# S3220B1.net
KiCad netlist of a schematic drawn in Altium Designer
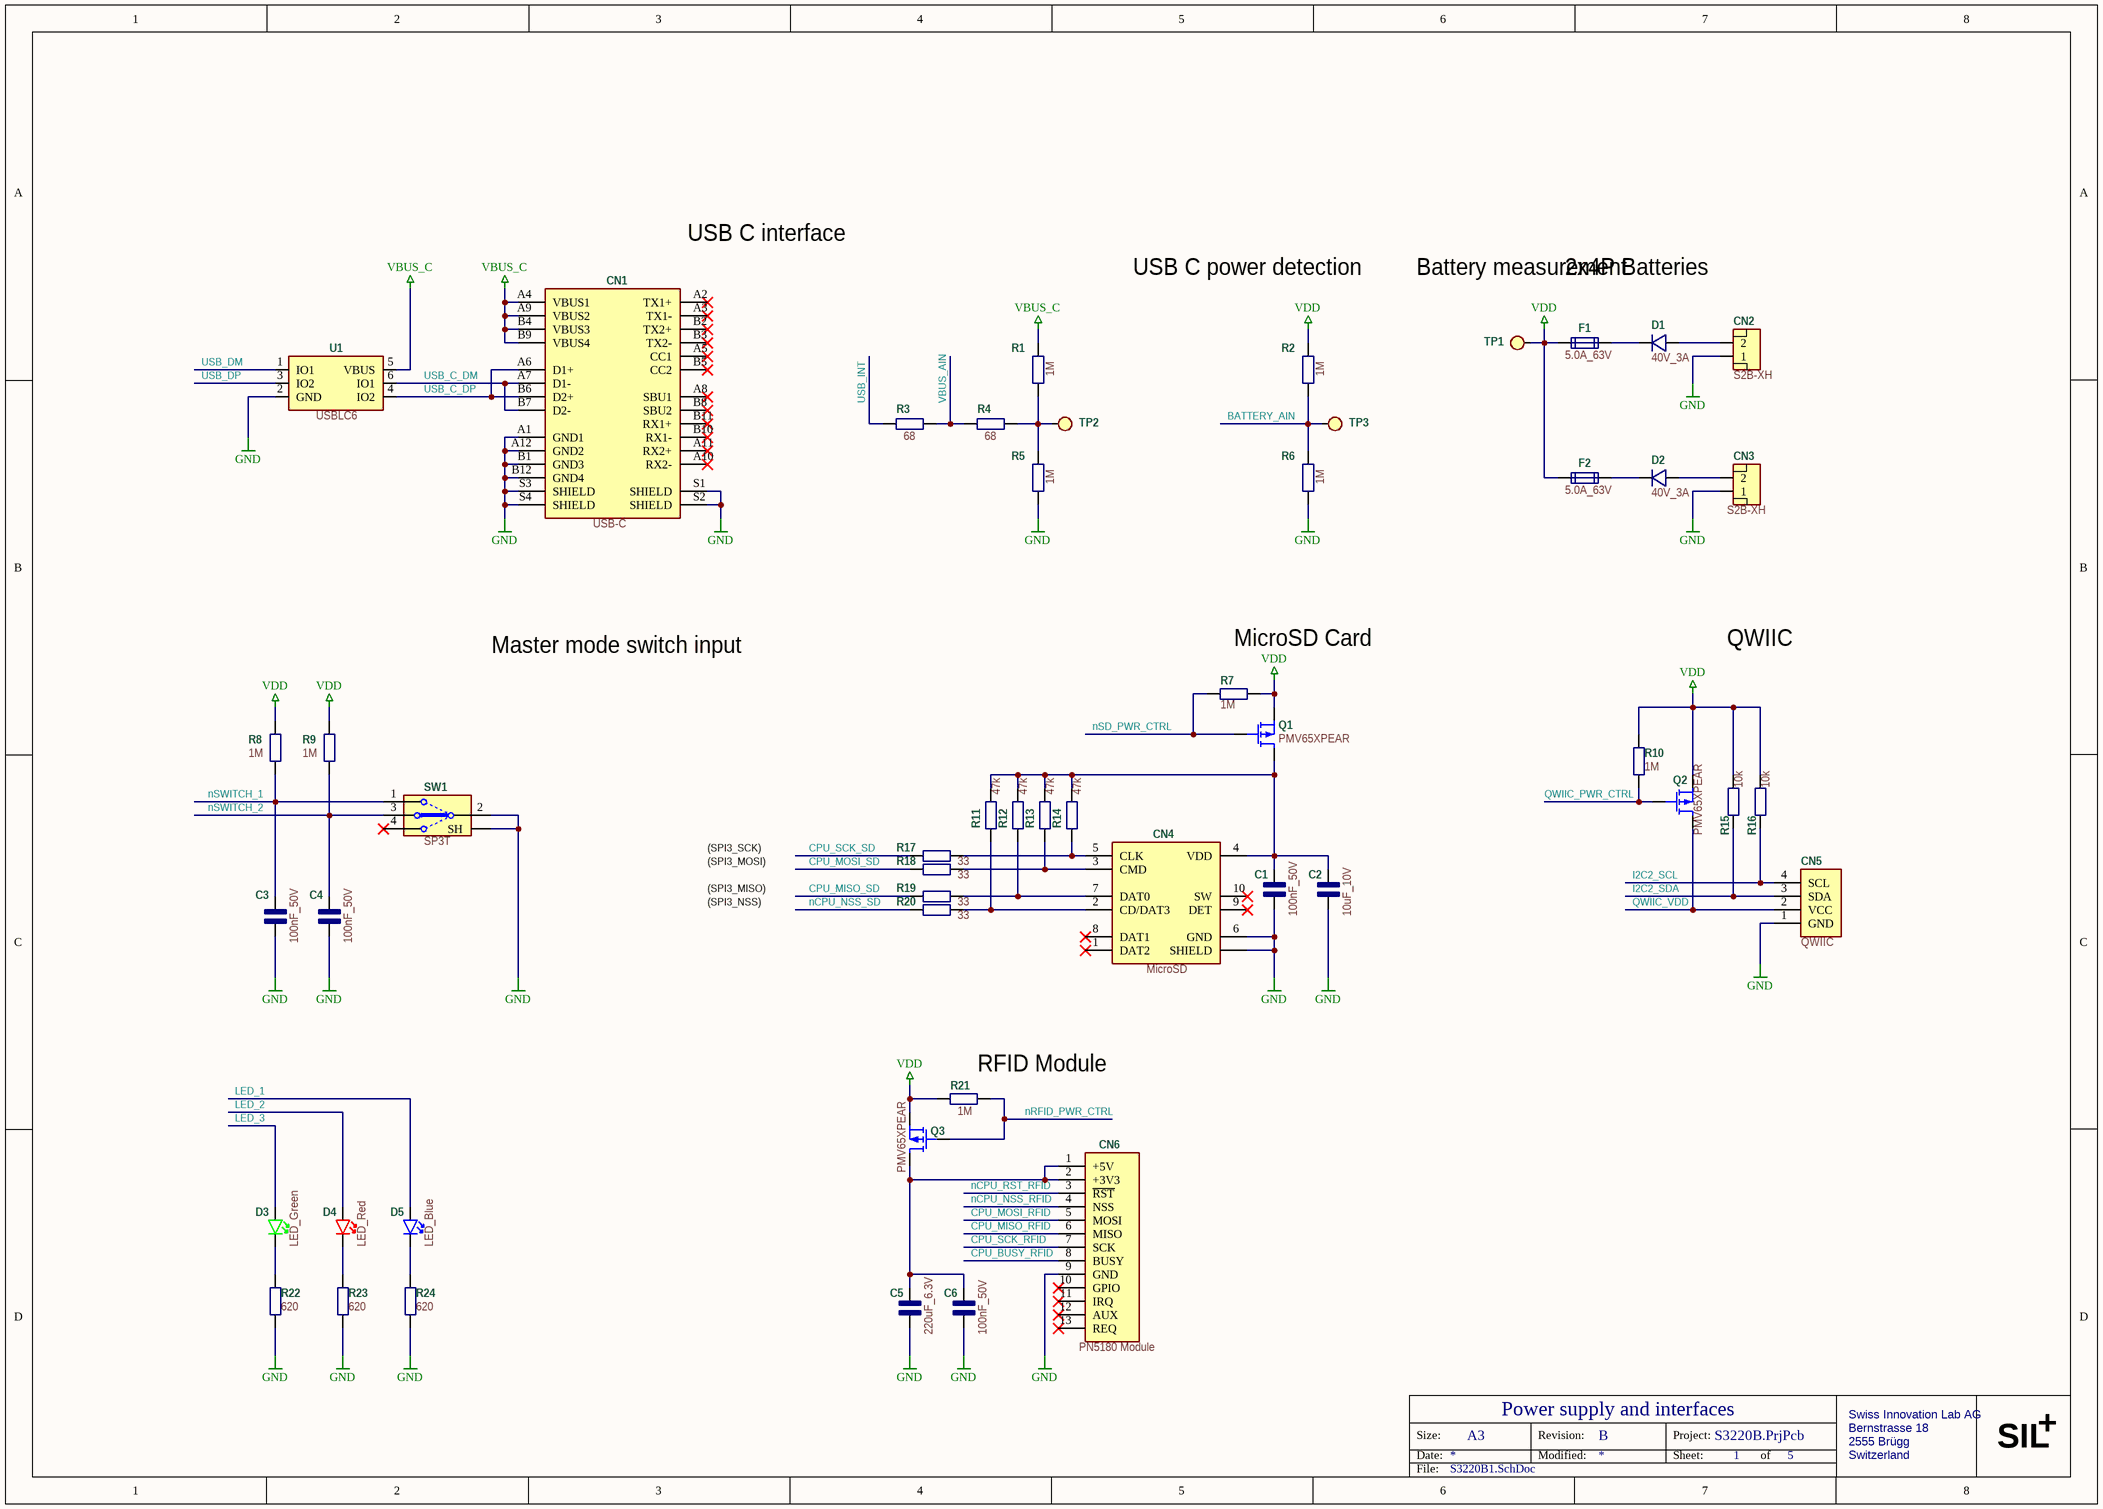
[diagram p0: S3220B1.SchDoc]

(export (version "E")
  (design (tool "Eeschema 10.0.6"))
  (components
    (comp (ref "C1")
      (value "100nF_50V")
      (footprint "SIL:C_0603")
      (description "0.1µF ±10% 50V Ceramic Capacitor X7R 0603 (1608 Metric)")
      (fields
        (field (name "MANUFACTURER") "TDK")
        (field (name "MANUFACTURER PART NUMBER") "C1608X7R1H104K080AA")
      )
      (libsource (lib "SIL") (part "C_100nF_50V"))
    )
    (comp (ref "C2")
      (value "10uF_10V")
      (footprint "SIL:C_0603")
      (description "10µF ±10% 10V Ceramic Capacitor X5R 0603 (1608 Metric)")
      (fields
        (field (name "MANUFACTURER") "Murata Electronics North America")
        (field (name "MANUFACTURER PART NUMBER") "GRM188R61A106KE69D")
      )
      (libsource (lib "SIL") (part "C_10uF_10V"))
    )
    (comp (ref "C3")
      (value "100nF_50V")
      (footprint "SIL:C_0603")
      (description "0.1µF ±10% 50V Ceramic Capacitor X7R 0603 (1608 Metric)")
      (fields
        (field (name "MANUFACTURER") "TDK")
        (field (name "MANUFACTURER PART NUMBER") "C1608X7R1H104K080AA")
      )
      (libsource (lib "SIL") (part "C_100nF_50V"))
    )
    (comp (ref "C4")
      (value "100nF_50V")
      (footprint "SIL:C_0603")
      (description "0.1µF ±10% 50V Ceramic Capacitor X7R 0603 (1608 Metric)")
      (fields
        (field (name "MANUFACTURER") "TDK")
        (field (name "MANUFACTURER PART NUMBER") "C1608X7R1H104K080AA")
      )
      (libsource (lib "SIL") (part "C_100nF_50V"))
    )
    (comp (ref "C5")
      (value "220uF_6.3V")
      (footprint "C_1206")
      (description "220µF ±20% 6.3V Ceramic Capacitor X5R 1206 (3216 Metric)")
      (fields
        (field (name "MANUFACTURER") "Murata Electronics North America")
        (field (name "MANUFACTURER PART NUMBER") "GRM31CR60J227ME11L")
      )
      (libsource (lib "SIL") (part "C_220uF_6.3V"))
    )
    (comp (ref "C6")
      (value "100nF_50V")
      (footprint "SIL:C_0603")
      (description "0.1µF ±10% 50V Ceramic Capacitor X7R 0603 (1608 Metric)")
      (fields
        (field (name "MANUFACTURER") "TDK")
        (field (name "MANUFACTURER PART NUMBER") "C1608X7R1H104K080AA")
      )
      (libsource (lib "SIL") (part "C_100nF_50V"))
    )
    (comp (ref "CN1")
      (value "USB-C")
      (footprint "CN_USB-C-RA_2")
      (fields
        (field (name "MANUFACTURER") "CUI Devices")
        (field (name "MANUFACTURER PART NUMBER") "UJ31-CH-G-SMT-TR-67")
      )
      (libsource (lib "SIL") (part "CN_USB-C-RA_2"))
    )
    (comp (ref "CN2")
      (value "S2B-XH")
      (footprint "CN_S2B-XH-A")
      (description "Connector Header Through Hole, Right Angle 2 position 0.098\" (2.50mm)")
      (fields
        (field (name "MANUFACTURER") "JST Sales America Inc.")
        (field (name "MANUFACTURER PART NUMBER") "S2B-XH-A(LF)(SN)")
      )
      (libsource (lib "SIL") (part "CN_S2B-XH"))
    )
    (comp (ref "CN3")
      (value "S2B-XH")
      (footprint "CN_S2B-XH-A")
      (description "Connector Header Through Hole, Right Angle 2 position 0.098\" (2.50mm)")
      (fields
        (field (name "MANUFACTURER") "JST Sales America Inc.")
        (field (name "MANUFACTURER PART NUMBER") "S2B-XH-A(LF)(SN)")
      )
      (libsource (lib "SIL") (part "CN_S2B-XH"))
    )
    (comp (ref "CN4")
      (value "MicroSD")
      (footprint "CN_MicroSD-Holder")
      (description "10 (8 + 2) Position Card Connector Secure Digital microSD Surface Mount, Right Angle Gold")
      (fields (field (name "MANUFACTURER") "Molex") (field (name "MANUFACTURER PART NUMBER") "5031821852"))
      (libsource (lib "SIL") (part "CN_MicroSD-Holder"))
    )
    (comp (ref "CN5")
      (value "QWIIC")
      (footprint "CN_SM04B-SRSS-TB")
      (description "Connector Header Surface Mount, Right Angle 4 position 0.039\" (1.00mm)")
      (fields
        (field (name "MANUFACTURER") "JST Sales America Inc.")
        (field (name "MANUFACTURER PART NUMBER") "SM04B-SRSS-TB(LF)(SN)")
      )
      (libsource (lib "SIL") (part "CN_QWICC"))
    )
    (comp (ref "CN6")
      (value "PN5180 Module")
      (footprint "CN_RFID-PN5180")
      (description "RFID Module PN5180")
      (fields
        (field (name "MANUFACTURER") "Swiss Innovation Lab")
        (field (name "MANUFACTURER PART NUMBER") "RFID-PN5180")
      )
      (libsource (lib "SIL") (part "CN_RFID-PN5180"))
    )
    (comp (ref "D1")
      (value "40V_3A")
      (footprint "D_DO-214AC")
      (description "Diode Schottky 40V 3A Surface Mount DO-214AC (SMA)")
      (fields
        (field (name "MANUFACTURER") "Comchip Technology")
        (field (name "MANUFACTURER PART NUMBER") "CDBA340L-HF")
      )
      (libsource (lib "SIL") (part "D_40V_3A"))
    )
    (comp (ref "D2")
      (value "40V_3A")
      (footprint "D_DO-214AC")
      (description "Diode Schottky 40V 3A Surface Mount DO-214AC (SMA)")
      (fields
        (field (name "MANUFACTURER") "Comchip Technology")
        (field (name "MANUFACTURER PART NUMBER") "CDBA340L-HF")
      )
      (libsource (lib "SIL") (part "D_40V_3A"))
    )
    (comp (ref "D3")
      (value "LED_Green")
      (footprint "LED_2-SMD_4x4")
      (description "Green 570nm LED Indication - Discrete 1.8V 2-SMD, Boomerang")
      (fields
        (field (name "MANUFACTURER") "OSRAM Opto Semiconductors Inc.")
        (field (name "MANUFACTURER PART NUMBER") "LG A67K-G2K1-24-0-2-R33-Z")
      )
      (libsource (lib "SIL") (part "D_LED_G_2mA"))
    )
    (comp (ref "D4")
      (value "LED_Red")
      (footprint "LED_2-SMD_4x4")
      (description "Red 630nm LED Indication - Discrete 1.8V 2-SMD, Boomerang")
      (fields
        (field (name "MANUFACTURER") "OSRAM Opto Semiconductors Inc.")
        (field (name "MANUFACTURER PART NUMBER") "LS A67K-J1K2-1-Z")
      )
      (libsource (lib "SIL") (part "D_LED_R_2mA"))
    )
    (comp (ref "D5")
      (value "LED_Blue")
      (footprint "LED_2-SMD_4x4")
      (description "Blue 471nm LED Indication - Discrete 3.1V 2-SMD, Boomerang")
      (fields
        (field (name "MANUFACTURER") "OSRAM Opto Semiconductors Inc.")
        (field (name "MANUFACTURER PART NUMBER") "LB A673-L2N1-35-Z")
      )
      (libsource (lib "SIL") (part "D_LED_B_10mA"))
    )
    (comp (ref "F1")
      (value "5.0A_63V")
      (footprint "F_1206")
      (description "FUSE BOARD MNT 5A 63VAC/VDC 1206")
      (fields (field (name "MANUFACTURER") "Bel Fuse Inc.") (field (name "MANUFACTURER PART NUMBER") "C1S 5"))
      (libsource (lib "SIL") (part "F_5A_63V"))
    )
    (comp (ref "F2")
      (value "5.0A_63V")
      (footprint "F_1206")
      (description "FUSE BOARD MNT 5A 63VAC/VDC 1206")
      (fields (field (name "MANUFACTURER") "Bel Fuse Inc.") (field (name "MANUFACTURER PART NUMBER") "C1S 5"))
      (libsource (lib "SIL") (part "F_5A_63V"))
    )
    (comp (ref "Q1")
      (value "PMV65XPEAR")
      (footprint "U_SOT23-3")
      (description "P-Channel 20V 2.8A (Ta) 480mW (Ta), 6.25W (Tc) Surface Mount TO-236AB (SOT23)")
      (fields (field (name "MANUFACTURER") "Nexperia USA Inc."))
      (libsource (lib "SIL") (part "Q_PMV65"))
    )
    (comp (ref "Q2")
      (value "PMV65XPEAR")
      (footprint "U_SOT23-3")
      (description "P-Channel 20V 2.8A (Ta) 480mW (Ta), 6.25W (Tc) Surface Mount TO-236AB (SOT23)")
      (fields (field (name "MANUFACTURER") "Nexperia USA Inc."))
      (libsource (lib "SIL") (part "Q_PMV65"))
    )
    (comp (ref "Q3")
      (value "PMV65XPEAR")
      (footprint "U_SOT23-3")
      (description "P-Channel 20V 2.8A (Ta) 480mW (Ta), 6.25W (Tc) Surface Mount TO-236AB (SOT23)")
      (fields (field (name "MANUFACTURER") "Nexperia USA Inc."))
      (libsource (lib "SIL") (part "Q_PMV65"))
    )
    (comp (ref "R1")
      (value "1M")
      (footprint "SIL:R_0603")
      (description "1 MOhms ±1% 0.1W, 1/10W Chip Resistor 0603 (1608 Metric) Automotive AEC-Q200 Thick Film")
      (fields
        (field (name "MANUFACTURER") "Panasonic Electronic Components")
        (field (name "MANUFACTURER PART NUMBER") "ERJ-3EKF1004V")
      )
      (libsource (lib "") (part "R_1M_1%_2"))
    )
    (comp (ref "R2")
      (value "1M")
      (footprint "SIL:R_0603")
      (description "1 MOhms ±1% 0.1W, 1/10W Chip Resistor 0603 (1608 Metric) Automotive AEC-Q200 Thick Film")
      (fields
        (field (name "MANUFACTURER") "Panasonic Electronic Components")
        (field (name "MANUFACTURER PART NUMBER") "ERJ-3EKF1004V")
      )
      (libsource (lib "") (part "R_1M_1%_2"))
    )
    (comp (ref "R3")
      (value "68")
      (footprint "SIL:R_0603")
      (description "68 Ohms ±1% 0.1W, 1/10W Chip Resistor 0603 (1608 Metric) Automotive AEC-Q200 Thick Film")
      (fields
        (field (name "MANUFACTURER") "Panasonic Electronic Components")
        (field (name "MANUFACTURER PART NUMBER") "ERJ-3EKF68R0V")
      )
      (libsource (lib "SIL") (part "R_68_1%"))
    )
    (comp (ref "R4")
      (value "68")
      (footprint "SIL:R_0603")
      (description "68 Ohms ±1% 0.1W, 1/10W Chip Resistor 0603 (1608 Metric) Automotive AEC-Q200 Thick Film")
      (fields
        (field (name "MANUFACTURER") "Panasonic Electronic Components")
        (field (name "MANUFACTURER PART NUMBER") "ERJ-3EKF68R0V")
      )
      (libsource (lib "SIL") (part "R_68_1%"))
    )
    (comp (ref "R5")
      (value "1M")
      (footprint "SIL:R_0603")
      (description "1 MOhms ±1% 0.1W, 1/10W Chip Resistor 0603 (1608 Metric) Automotive AEC-Q200 Thick Film")
      (fields
        (field (name "MANUFACTURER") "Panasonic Electronic Components")
        (field (name "MANUFACTURER PART NUMBER") "ERJ-3EKF1004V")
      )
      (libsource (lib "") (part "R_1M_1%_2"))
    )
    (comp (ref "R6")
      (value "1M")
      (footprint "SIL:R_0603")
      (description "1 MOhms ±1% 0.1W, 1/10W Chip Resistor 0603 (1608 Metric) Automotive AEC-Q200 Thick Film")
      (fields
        (field (name "MANUFACTURER") "Panasonic Electronic Components")
        (field (name "MANUFACTURER PART NUMBER") "ERJ-3EKF1004V")
      )
      (libsource (lib "") (part "R_1M_1%_2"))
    )
    (comp (ref "R7")
      (value "1M")
      (footprint "SIL:R_0603")
      (description "1 MOhms ±1% 0.1W, 1/10W Chip Resistor 0603 (1608 Metric) Automotive AEC-Q200 Thick Film")
      (fields
        (field (name "MANUFACTURER") "Panasonic Electronic Components")
        (field (name "MANUFACTURER PART NUMBER") "ERJ-3EKF1004V")
      )
      (libsource (lib "") (part "R_1M_1%_1"))
    )
    (comp (ref "R8")
      (value "1M")
      (footprint "SIL:R_0603")
      (description "1 MOhms ±1% 0.1W, 1/10W Chip Resistor 0603 (1608 Metric) Automotive AEC-Q200 Thick Film")
      (fields
        (field (name "MANUFACTURER") "Panasonic Electronic Components")
        (field (name "MANUFACTURER PART NUMBER") "ERJ-3EKF1004V")
      )
      (libsource (lib "") (part "R_1M_1%_2"))
    )
    (comp (ref "R9")
      (value "1M")
      (footprint "SIL:R_0603")
      (description "1 MOhms ±1% 0.1W, 1/10W Chip Resistor 0603 (1608 Metric) Automotive AEC-Q200 Thick Film")
      (fields
        (field (name "MANUFACTURER") "Panasonic Electronic Components")
        (field (name "MANUFACTURER PART NUMBER") "ERJ-3EKF1004V")
      )
      (libsource (lib "") (part "R_1M_1%_2"))
    )
    (comp (ref "R10")
      (value "1M")
      (footprint "SIL:R_0603")
      (description "1 MOhms ±1% 0.1W, 1/10W Chip Resistor 0603 (1608 Metric) Automotive AEC-Q200 Thick Film")
      (fields
        (field (name "MANUFACTURER") "Panasonic Electronic Components")
        (field (name "MANUFACTURER PART NUMBER") "ERJ-3EKF1004V")
      )
      (libsource (lib "") (part "R_1M_1%_2"))
    )
    (comp (ref "R11")
      (value "47k")
      (footprint "SIL:R_0603")
      (description "47 kOhms ±1% 0.1W, 1/10W Chip Resistor 0603 (1608 Metric) Automotive AEC-Q200 Thick Film")
      (fields
        (field (name "MANUFACTURER") "Panasonic Electronic Components")
        (field (name "MANUFACTURER PART NUMBER") "ERJ-3EKF4702V")
      )
      (libsource (lib "SIL") (part "R_47k_1%"))
    )
    (comp (ref "R12")
      (value "47k")
      (footprint "SIL:R_0603")
      (description "47 kOhms ±1% 0.1W, 1/10W Chip Resistor 0603 (1608 Metric) Automotive AEC-Q200 Thick Film")
      (fields
        (field (name "MANUFACTURER") "Panasonic Electronic Components")
        (field (name "MANUFACTURER PART NUMBER") "ERJ-3EKF4702V")
      )
      (libsource (lib "SIL") (part "R_47k_1%"))
    )
    (comp (ref "R13")
      (value "47k")
      (footprint "SIL:R_0603")
      (description "47 kOhms ±1% 0.1W, 1/10W Chip Resistor 0603 (1608 Metric) Automotive AEC-Q200 Thick Film")
      (fields
        (field (name "MANUFACTURER") "Panasonic Electronic Components")
        (field (name "MANUFACTURER PART NUMBER") "ERJ-3EKF4702V")
      )
      (libsource (lib "SIL") (part "R_47k_1%"))
    )
    (comp (ref "R14")
      (value "47k")
      (footprint "SIL:R_0603")
      (description "47 kOhms ±1% 0.1W, 1/10W Chip Resistor 0603 (1608 Metric) Automotive AEC-Q200 Thick Film")
      (fields
        (field (name "MANUFACTURER") "Panasonic Electronic Components")
        (field (name "MANUFACTURER PART NUMBER") "ERJ-3EKF4702V")
      )
      (libsource (lib "SIL") (part "R_47k_1%"))
    )
    (comp (ref "R15")
      (value "10k")
      (footprint "SIL:R_0603")
      (description "10 kOhms ±1% 0.1W, 1/10W Chip Resistor 0603 (1608 Metric) Automotive AEC-Q200 Thick Film")
      (fields
        (field (name "MANUFACTURER") "Panasonic Electronic Components")
        (field (name "MANUFACTURER PART NUMBER") "ERJ-3EKF1002V")
      )
      (libsource (lib "SIL") (part "R_10k_1%"))
    )
    (comp (ref "R16")
      (value "10k")
      (footprint "SIL:R_0603")
      (description "10 kOhms ±1% 0.1W, 1/10W Chip Resistor 0603 (1608 Metric) Automotive AEC-Q200 Thick Film")
      (fields
        (field (name "MANUFACTURER") "Panasonic Electronic Components")
        (field (name "MANUFACTURER PART NUMBER") "ERJ-3EKF1002V")
      )
      (libsource (lib "SIL") (part "R_10k_1%"))
    )
    (comp (ref "R17")
      (value "33")
      (footprint "SIL:R_0603")
      (description "33 Ohms ±1% 0.1W, 1/10W Chip Resistor 0603 (1608 Metric) Automotive AEC-Q200 Thick Film")
      (fields
        (field (name "MANUFACTURER") "Panasonic Electronic Components")
        (field (name "MANUFACTURER PART NUMBER") "ERJ-3EKF33R0V")
      )
      (libsource (lib "SIL") (part "R_33_1%"))
    )
    (comp (ref "R18")
      (value "33")
      (footprint "SIL:R_0603")
      (description "33 Ohms ±1% 0.1W, 1/10W Chip Resistor 0603 (1608 Metric) Automotive AEC-Q200 Thick Film")
      (fields
        (field (name "MANUFACTURER") "Panasonic Electronic Components")
        (field (name "MANUFACTURER PART NUMBER") "ERJ-3EKF33R0V")
      )
      (libsource (lib "SIL") (part "R_33_1%"))
    )
    (comp (ref "R19")
      (value "33")
      (footprint "SIL:R_0603")
      (description "33 Ohms ±1% 0.1W, 1/10W Chip Resistor 0603 (1608 Metric) Automotive AEC-Q200 Thick Film")
      (fields
        (field (name "MANUFACTURER") "Panasonic Electronic Components")
        (field (name "MANUFACTURER PART NUMBER") "ERJ-3EKF33R0V")
      )
      (libsource (lib "SIL") (part "R_33_1%"))
    )
    (comp (ref "R20")
      (value "33")
      (footprint "SIL:R_0603")
      (description "33 Ohms ±1% 0.1W, 1/10W Chip Resistor 0603 (1608 Metric) Automotive AEC-Q200 Thick Film")
      (fields
        (field (name "MANUFACTURER") "Panasonic Electronic Components")
        (field (name "MANUFACTURER PART NUMBER") "ERJ-3EKF33R0V")
      )
      (libsource (lib "SIL") (part "R_33_1%"))
    )
    (comp (ref "R21")
      (value "1M")
      (footprint "SIL:R_0603")
      (description "1 MOhms ±1% 0.1W, 1/10W Chip Resistor 0603 (1608 Metric) Automotive AEC-Q200 Thick Film")
      (fields
        (field (name "MANUFACTURER") "Panasonic Electronic Components")
        (field (name "MANUFACTURER PART NUMBER") "ERJ-3EKF1004V")
      )
      (libsource (lib "SIL") (part "R_1M_1%"))
    )
    (comp (ref "R22")
      (value "620")
      (footprint "SIL:R_0603")
      (description "620 Ohms ±1% 0.1W, 1/10W Chip Resistor 0603 (1608 Metric) Automotive AEC-Q200 Thick Film")
      (fields
        (field (name "MANUFACTURER") "Panasonic Electronic Components")
        (field (name "MANUFACTURER PART NUMBER") "ERJ-3EKF6200V")
      )
      (libsource (lib "SIL") (part "R_620_1%"))
    )
    (comp (ref "R23")
      (value "620")
      (footprint "SIL:R_0603")
      (description "620 Ohms ±1% 0.1W, 1/10W Chip Resistor 0603 (1608 Metric) Automotive AEC-Q200 Thick Film")
      (fields
        (field (name "MANUFACTURER") "Panasonic Electronic Components")
        (field (name "MANUFACTURER PART NUMBER") "ERJ-3EKF6200V")
      )
      (libsource (lib "SIL") (part "R_620_1%"))
    )
    (comp (ref "R24")
      (value "620")
      (footprint "SIL:R_0603")
      (description "620 Ohms ±1% 0.1W, 1/10W Chip Resistor 0603 (1608 Metric) Automotive AEC-Q200 Thick Film")
      (fields
        (field (name "MANUFACTURER") "Panasonic Electronic Components")
        (field (name "MANUFACTURER PART NUMBER") "ERJ-3EKF6200V")
      )
      (libsource (lib "SIL") (part "R_620_1%"))
    )
    (comp (ref "SW1")
      (value "SP3T")
      (footprint "SW_SLIDE-SP3T")
      (description "Slide Switch SP3T Through Hole, Right Angle")
      (fields (field (name "MANUFACTURER") "C&K") (field (name "MANUFACTURER PART NUMBER") "OS103011MA7QP1"))
      (libsource (lib "SIL") (part "SW_SP3T_Slide"))
    )
    (comp (ref "TP1")
      (value "Test point")
      (footprint "SIL:TP_SMD_R1.0mm")
      (fields (field (name "MANUFACTURER") "Swiss Innovation Lab"))
      (libsource (lib "SIL") (part "TP_Test_point"))
    )
    (comp (ref "TP2")
      (value "Test point")
      (footprint "SIL:TP_SMD_R1.0mm")
      (fields (field (name "MANUFACTURER") "Swiss Innovation Lab"))
      (libsource (lib "SIL") (part "TP_Test_point"))
    )
    (comp (ref "TP3")
      (value "Test point")
      (footprint "SIL:TP_SMD_R1.0mm")
      (fields (field (name "MANUFACTURER") "Swiss Innovation Lab"))
      (libsource (lib "SIL") (part "TP_Test_point"))
    )
    (comp (ref "U1")
      (value "USBLC6")
      (footprint "U_SOT23-6")
      (description "TVS DIODE 5.25V 17V SOT23-6")
      (fields
        (field (name "MANUFACTURER") "STMicroelectronics")
        (field (name "MANUFACTURER PART NUMBER") "USBLC6-2SC6Y")
      )
      (libsource (lib "SIL") (part "U_USBLC6"))
    )
  )
  (nets
    (net (code "1") (name "/BATTERY_AIN") (class "Default")
      (node (ref "R2") (pin "1") (pinfunction "1_1") (pintype "passive"))
      (node (ref "R6") (pin "2") (pinfunction "2_2") (pintype "passive"))
      (node (ref "TP3") (pin "1") (pinfunction "1_1") (pintype "passive"))
    )
    (net (code "2") (name "/CPU_BUSY_RFID") (class "Default")
      (node (ref "CN6") (pin "8") (pinfunction "BUSY_8") (pintype "passive"))
    )
    (net (code "3") (name "/CPU_MISO_RFID") (class "Default")
      (node (ref "CN6") (pin "6") (pinfunction "MISO_6") (pintype "passive"))
    )
    (net (code "4") (name "/CPU_MISO_SD") (class "Default")
      (node (ref "R19") (pin "1") (pinfunction "1_1") (pintype "passive"))
    )
    (net (code "5") (name "/CPU_MOSI_RFID") (class "Default")
      (node (ref "CN6") (pin "5") (pinfunction "MOSI_5") (pintype "passive"))
    )
    (net (code "6") (name "/CPU_MOSI_SD") (class "Default")
      (node (ref "R18") (pin "1") (pinfunction "1_1") (pintype "passive"))
    )
    (net (code "7") (name "/CPU_SCK_RFID") (class "Default")
      (node (ref "CN6") (pin "7") (pinfunction "SCK_7") (pintype "passive"))
    )
    (net (code "8") (name "/CPU_SCK_SD") (class "Default")
      (node (ref "R17") (pin "1") (pinfunction "1_1") (pintype "passive"))
    )
    (net (code "9") (name "/I2C2_SCL") (class "Default")
      (node (ref "CN5") (pin "4") (pinfunction "SCL_4") (pintype "passive"))
      (node (ref "R16") (pin "1") (pinfunction "1_1") (pintype "passive"))
    )
    (net (code "10") (name "/I2C2_SDA") (class "Default")
      (node (ref "CN5") (pin "3") (pinfunction "SDA_3") (pintype "passive"))
      (node (ref "R15") (pin "1") (pinfunction "1_1") (pintype "passive"))
    )
    (net (code "11") (name "/LED_1") (class "Default")
      (node (ref "D5") (pin "1") (pinfunction "A_1") (pintype "passive"))
    )
    (net (code "12") (name "/LED_2") (class "Default")
      (node (ref "D4") (pin "1") (pinfunction "A_1") (pintype "passive"))
    )
    (net (code "13") (name "/LED_3") (class "Default")
      (node (ref "D3") (pin "1") (pinfunction "A_1") (pintype "passive"))
    )
    (net (code "14") (name "/QWIIC_PWR_CTRL") (class "Default")
      (node (ref "Q2") (pin "1") (pinfunction "G_1") (pintype "passive"))
      (node (ref "R10") (pin "1") (pinfunction "1_1") (pintype "passive"))
    )
    (net (code "15") (name "/QWIIC_VDD") (class "Default")
      (node (ref "CN5") (pin "2") (pinfunction "VCC_2") (pintype "passive"))
      (node (ref "Q2") (pin "3") (pinfunction "D_3") (pintype "passive"))
    )
    (net (code "16") (name "/USB_C_DM") (class "Default")
      (node (ref "CN1") (pin "A7") (pinfunction "D1-_A7") (pintype "passive"))
      (node (ref "CN1") (pin "B7") (pinfunction "D2-_B7") (pintype "passive"))
      (node (ref "U1") (pin "6") (pinfunction "IO1_6") (pintype "passive"))
    )
    (net (code "17") (name "/USB_C_DP") (class "Default")
      (node (ref "CN1") (pin "A6") (pinfunction "D1+_A6") (pintype "passive"))
      (node (ref "CN1") (pin "B6") (pinfunction "D2+_B6") (pintype "passive"))
      (node (ref "U1") (pin "4") (pinfunction "IO2_4") (pintype "passive"))
    )
    (net (code "18") (name "/USB_DM") (class "Default")
      (node (ref "U1") (pin "1") (pinfunction "IO1_1") (pintype "passive"))
    )
    (net (code "19") (name "/USB_DP") (class "Default")
      (node (ref "U1") (pin "3") (pinfunction "IO2_3") (pintype "passive"))
    )
    (net (code "20") (name "/USB_INT") (class "Default")
      (node (ref "R3") (pin "1") (pinfunction "1_1") (pintype "passive"))
    )
    (net (code "21") (name "/VBUS_AIN") (class "Default")
      (node (ref "R3") (pin "2") (pinfunction "2_2") (pintype "passive"))
      (node (ref "R4") (pin "1") (pinfunction "1_1") (pintype "passive"))
    )
    (net (code "22") (name "/nCPU_NSS_RFID") (class "Default")
      (node (ref "CN6") (pin "4") (pinfunction "NSS_4") (pintype "passive"))
    )
    (net (code "23") (name "/nCPU_NSS_SD") (class "Default")
      (node (ref "R20") (pin "1") (pinfunction "1_1") (pintype "passive"))
    )
    (net (code "24") (name "/nCPU_RST_RFID") (class "Default")
      (node (ref "CN6") (pin "3") (pinfunction "~{RST}_3") (pintype "passive"))
    )
    (net (code "25") (name "/nRFID_PWR_CTRL") (class "Default")
      (node (ref "Q3") (pin "1") (pinfunction "G_1") (pintype "passive"))
      (node (ref "R21") (pin "2") (pinfunction "2_2") (pintype "passive"))
    )
    (net (code "26") (name "/nSD_PWR_CTRL") (class "Default")
      (node (ref "Q1") (pin "1") (pinfunction "G_1") (pintype "passive"))
      (node (ref "R7") (pin "2") (pinfunction "2_2") (pintype "passive"))
    )
    (net (code "27") (name "/nSWITCH_1") (class "Default")
      (node (ref "C3") (pin "2") (pintype "passive"))
      (node (ref "R8") (pin "1") (pinfunction "1_1") (pintype "passive"))
      (node (ref "SW1") (pin "1") (pinfunction "1_1") (pintype "passive"))
    )
    (net (code "28") (name "/nSWITCH_2") (class "Default")
      (node (ref "C4") (pin "2") (pintype "passive"))
      (node (ref "R9") (pin "1") (pinfunction "1_1") (pintype "passive"))
      (node (ref "SW1") (pin "3") (pinfunction "3_3") (pintype "passive"))
    )
    (net (code "29") (name "GND") (class "Default")
      (node (ref "C1") (pin "1") (pintype "passive"))
      (node (ref "C2") (pin "1") (pintype "passive"))
      (node (ref "C3") (pin "1") (pintype "passive"))
      (node (ref "C4") (pin "1") (pintype "passive"))
      (node (ref "C5") (pin "1") (pintype "passive"))
      (node (ref "C6") (pin "1") (pintype "passive"))
      (node (ref "CN1") (pin "A1") (pinfunction "GND1_A1") (pintype "power_in"))
      (node (ref "CN1") (pin "A12") (pinfunction "GND2_A12") (pintype "power_in"))
      (node (ref "CN1") (pin "B1") (pinfunction "GND3_B1") (pintype "power_in"))
      (node (ref "CN1") (pin "B12") (pinfunction "GND4_B12") (pintype "power_in"))
      (node (ref "CN1") (pin "S1") (pinfunction "SHIELD_S1") (pintype "power_in"))
      (node (ref "CN1") (pin "S2") (pinfunction "SHIELD_S2") (pintype "power_in"))
      (node (ref "CN1") (pin "S3") (pinfunction "SHIELD_S3") (pintype "power_in"))
      (node (ref "CN1") (pin "S4") (pinfunction "SHIELD_S4") (pintype "power_in"))
      (node (ref "CN2") (pin "1") (pinfunction "1_1") (pintype "passive"))
      (node (ref "CN3") (pin "1") (pinfunction "1_1") (pintype "passive"))
      (node (ref "CN4") (pin "0") (pinfunction "SHIELD_0") (pintype "passive"))
      (node (ref "CN4") (pin "6") (pinfunction "GND_6") (pintype "passive"))
      (node (ref "CN5") (pin "1") (pinfunction "GND_1") (pintype "passive"))
      (node (ref "CN6") (pin "9") (pinfunction "GND_9") (pintype "power_in"))
      (node (ref "R22") (pin "2") (pinfunction "2_2") (pintype "passive"))
      (node (ref "R23") (pin "2") (pinfunction "2_2") (pintype "passive"))
      (node (ref "R24") (pin "2") (pinfunction "2_2") (pintype "passive"))
      (node (ref "R5") (pin "1") (pinfunction "1_1") (pintype "passive"))
      (node (ref "R6") (pin "1") (pinfunction "1_1") (pintype "passive"))
      (node (ref "SW1") (pin "0") (pinfunction "SH_0") (pintype "passive"))
      (node (ref "SW1") (pin "2") (pinfunction "2_2") (pintype "passive"))
      (node (ref "U1") (pin "2") (pinfunction "GND_2") (pintype "power_in"))
    )
    (net (code "30") (name "Net-(CN2-Pad2)") (class "Default")
      (node (ref "CN2") (pin "2") (pinfunction "2_2") (pintype "passive"))
      (node (ref "D1") (pin "A") (pintype "passive"))
    )
    (net (code "31") (name "Net-(CN3-Pad2)") (class "Default")
      (node (ref "CN3") (pin "2") (pinfunction "2_2") (pintype "passive"))
      (node (ref "D2") (pin "A") (pintype "passive"))
    )
    (net (code "32") (name "Net-(CN4-CD{slash}DAT3)") (class "Default")
      (node (ref "CN4") (pin "2") (pinfunction "CD/DAT3_2") (pintype "passive"))
      (node (ref "R11") (pin "1") (pinfunction "1_1") (pintype "passive"))
      (node (ref "R20") (pin "2") (pinfunction "2_2") (pintype "passive"))
    )
    (net (code "33") (name "Net-(CN4-CLK)") (class "Default")
      (node (ref "CN4") (pin "5") (pinfunction "CLK_5") (pintype "passive"))
      (node (ref "R14") (pin "1") (pinfunction "1_1") (pintype "passive"))
      (node (ref "R17") (pin "2") (pinfunction "2_2") (pintype "passive"))
    )
    (net (code "34") (name "Net-(CN4-CMD)") (class "Default")
      (node (ref "CN4") (pin "3") (pinfunction "CMD_3") (pintype "passive"))
      (node (ref "R13") (pin "1") (pinfunction "1_1") (pintype "passive"))
      (node (ref "R18") (pin "2") (pinfunction "2_2") (pintype "passive"))
    )
    (net (code "35") (name "Net-(CN4-DAT0)") (class "Default")
      (node (ref "CN4") (pin "7") (pinfunction "DAT0_7") (pintype "passive"))
      (node (ref "R12") (pin "1") (pinfunction "1_1") (pintype "passive"))
      (node (ref "R19") (pin "2") (pinfunction "2_2") (pintype "passive"))
    )
    (net (code "36") (name "Net-(CN4-VDD)") (class "Default")
      (node (ref "C1") (pin "2") (pintype "passive"))
      (node (ref "C2") (pin "2") (pintype "passive"))
      (node (ref "CN4") (pin "4") (pinfunction "VDD_4") (pintype "passive"))
      (node (ref "Q1") (pin "3") (pinfunction "D_3") (pintype "passive"))
      (node (ref "R11") (pin "2") (pinfunction "2_2") (pintype "passive"))
      (node (ref "R12") (pin "2") (pinfunction "2_2") (pintype "passive"))
      (node (ref "R13") (pin "2") (pinfunction "2_2") (pintype "passive"))
      (node (ref "R14") (pin "2") (pinfunction "2_2") (pintype "passive"))
    )
    (net (code "37") (name "Net-(CN6-+3V3)") (class "Default")
      (node (ref "C5") (pin "2") (pintype "passive"))
      (node (ref "C6") (pin "2") (pintype "passive"))
      (node (ref "CN6") (pin "1") (pinfunction "+5V_1") (pintype "power_in"))
      (node (ref "CN6") (pin "2") (pinfunction "+3V3_2") (pintype "power_in"))
      (node (ref "Q3") (pin "3") (pinfunction "D_3") (pintype "passive"))
    )
    (net (code "38") (name "Net-(D1-PadK)") (class "Default")
      (node (ref "D1") (pin "K") (pintype "passive"))
      (node (ref "F1") (pin "2") (pinfunction "2_2") (pintype "passive"))
    )
    (net (code "39") (name "Net-(D2-PadK)") (class "Default")
      (node (ref "D2") (pin "K") (pintype "passive"))
      (node (ref "F2") (pin "2") (pinfunction "2_2") (pintype "passive"))
    )
    (net (code "40") (name "Net-(D3-K)") (class "Default")
      (node (ref "D3") (pin "2") (pinfunction "K_2") (pintype "passive"))
      (node (ref "R22") (pin "1") (pinfunction "1_1") (pintype "passive"))
    )
    (net (code "41") (name "Net-(D4-K)") (class "Default")
      (node (ref "D4") (pin "2") (pinfunction "K_2") (pintype "passive"))
      (node (ref "R23") (pin "1") (pinfunction "1_1") (pintype "passive"))
    )
    (net (code "42") (name "Net-(D5-K)") (class "Default")
      (node (ref "D5") (pin "2") (pinfunction "K_2") (pintype "passive"))
      (node (ref "R24") (pin "1") (pinfunction "1_1") (pintype "passive"))
    )
    (net (code "43") (name "Net-(R1-Pad1)") (class "Default")
      (node (ref "R1") (pin "1") (pinfunction "1_1") (pintype "passive"))
      (node (ref "R4") (pin "2") (pinfunction "2_2") (pintype "passive"))
      (node (ref "R5") (pin "2") (pinfunction "2_2") (pintype "passive"))
      (node (ref "TP2") (pin "1") (pinfunction "1_1") (pintype "passive"))
    )
    (net (code "44") (name "VBUS_C") (class "Default")
      (node (ref "CN1") (pin "A4") (pinfunction "VBUS1_A4") (pintype "power_in"))
      (node (ref "CN1") (pin "A9") (pinfunction "VBUS2_A9") (pintype "power_in"))
      (node (ref "CN1") (pin "B4") (pinfunction "VBUS3_B4") (pintype "power_in"))
      (node (ref "CN1") (pin "B9") (pinfunction "VBUS4_B9") (pintype "power_in"))
      (node (ref "R1") (pin "2") (pinfunction "2_2") (pintype "passive"))
      (node (ref "U1") (pin "5") (pinfunction "VBUS_5") (pintype "power_in"))
    )
    (net (code "45") (name "VDD") (class "Default")
      (node (ref "F1") (pin "1") (pinfunction "1_1") (pintype "passive"))
      (node (ref "F2") (pin "1") (pinfunction "1_1") (pintype "passive"))
      (node (ref "Q1") (pin "2") (pinfunction "S_2") (pintype "passive"))
      (node (ref "Q2") (pin "2") (pinfunction "S_2") (pintype "passive"))
      (node (ref "Q3") (pin "2") (pinfunction "S_2") (pintype "passive"))
      (node (ref "R10") (pin "2") (pinfunction "2_2") (pintype "passive"))
      (node (ref "R15") (pin "2") (pinfunction "2_2") (pintype "passive"))
      (node (ref "R16") (pin "2") (pinfunction "2_2") (pintype "passive"))
      (node (ref "R2") (pin "2") (pinfunction "2_2") (pintype "passive"))
      (node (ref "R21") (pin "1") (pinfunction "1_1") (pintype "passive"))
      (node (ref "R7") (pin "1") (pinfunction "1_1") (pintype "passive"))
      (node (ref "R8") (pin "2") (pinfunction "2_2") (pintype "passive"))
      (node (ref "R9") (pin "2") (pinfunction "2_2") (pintype "passive"))
      (node (ref "TP1") (pin "1") (pinfunction "1_1") (pintype "passive"))
    )
    (net (code "46") (name "unconnected-(CN1-CC1-PadA5)") (class "Default")
      (node (ref "CN1") (pin "A5") (pinfunction "CC1_A5") (pintype "passive+no_connect"))
    )
    (net (code "47") (name "unconnected-(CN1-CC2-PadB5)") (class "Default")
      (node (ref "CN1") (pin "B5") (pinfunction "CC2_B5") (pintype "passive+no_connect"))
    )
    (net (code "48") (name "unconnected-(CN1-RX1+-PadB11)") (class "Default")
      (node (ref "CN1") (pin "B11") (pinfunction "RX1+_B11") (pintype "passive+no_connect"))
    )
    (net (code "49") (name "unconnected-(CN1-RX1--PadB10)") (class "Default")
      (node (ref "CN1") (pin "B10") (pinfunction "RX1-_B10") (pintype "passive+no_connect"))
    )
    (net (code "50") (name "unconnected-(CN1-RX2+-PadA11)") (class "Default")
      (node (ref "CN1") (pin "A11") (pinfunction "RX2+_A11") (pintype "passive+no_connect"))
    )
    (net (code "51") (name "unconnected-(CN1-RX2--PadA10)") (class "Default")
      (node (ref "CN1") (pin "A10") (pinfunction "RX2-_A10") (pintype "passive+no_connect"))
    )
    (net (code "52") (name "unconnected-(CN1-SBU1-PadA8)") (class "Default")
      (node (ref "CN1") (pin "A8") (pinfunction "SBU1_A8") (pintype "passive+no_connect"))
    )
    (net (code "53") (name "unconnected-(CN1-SBU2-PadB8)") (class "Default")
      (node (ref "CN1") (pin "B8") (pinfunction "SBU2_B8") (pintype "passive+no_connect"))
    )
    (net (code "54") (name "unconnected-(CN1-TX1+-PadA2)") (class "Default")
      (node (ref "CN1") (pin "A2") (pinfunction "TX1+_A2") (pintype "passive+no_connect"))
    )
    (net (code "55") (name "unconnected-(CN1-TX1--PadA3)") (class "Default")
      (node (ref "CN1") (pin "A3") (pinfunction "TX1-_A3") (pintype "passive+no_connect"))
    )
    (net (code "56") (name "unconnected-(CN1-TX2+-PadB2)") (class "Default")
      (node (ref "CN1") (pin "B2") (pinfunction "TX2+_B2") (pintype "passive+no_connect"))
    )
    (net (code "57") (name "unconnected-(CN1-TX2--PadB3)") (class "Default")
      (node (ref "CN1") (pin "B3") (pinfunction "TX2-_B3") (pintype "passive+no_connect"))
    )
    (net (code "58") (name "unconnected-(CN4-DAT1-Pad8)") (class "Default")
      (node (ref "CN4") (pin "8") (pinfunction "DAT1_8") (pintype "passive+no_connect"))
    )
    (net (code "59") (name "unconnected-(CN4-DAT2-Pad1)") (class "Default")
      (node (ref "CN4") (pin "1") (pinfunction "DAT2_1") (pintype "passive+no_connect"))
    )
    (net (code "60") (name "unconnected-(CN4-DET-Pad9)") (class "Default")
      (node (ref "CN4") (pin "9") (pinfunction "DET_9") (pintype "passive+no_connect"))
    )
    (net (code "61") (name "unconnected-(CN4-PadX1)") (class "Default")
      (node (ref "CN4") (pin "X1") (pinfunction "X1_X1") (pintype "passive"))
    )
    (net (code "62") (name "unconnected-(CN4-PadX2)") (class "Default")
      (node (ref "CN4") (pin "X2") (pinfunction "X2_X2") (pintype "passive"))
    )
    (net (code "63") (name "unconnected-(CN4-SW-Pad10)") (class "Default")
      (node (ref "CN4") (pin "10") (pinfunction "SW_10") (pintype "passive+no_connect"))
    )
    (net (code "64") (name "unconnected-(CN6-AUX-Pad12)") (class "Default")
      (node (ref "CN6") (pin "12") (pinfunction "AUX_12") (pintype "passive+no_connect"))
    )
    (net (code "65") (name "unconnected-(CN6-GPIO-Pad10)") (class "Default")
      (node (ref "CN6") (pin "10") (pinfunction "GPIO_10") (pintype "passive+no_connect"))
    )
    (net (code "66") (name "unconnected-(CN6-IRQ-Pad11)") (class "Default")
      (node (ref "CN6") (pin "11") (pinfunction "IRQ_11") (pintype "passive+no_connect"))
    )
    (net (code "67") (name "unconnected-(CN6-REQ-Pad13)") (class "Default")
      (node (ref "CN6") (pin "13") (pinfunction "REQ_13") (pintype "passive+no_connect"))
    )
    (net (code "68") (name "unconnected-(SW1-Pad4)") (class "Default")
      (node (ref "SW1") (pin "4") (pinfunction "4_4") (pintype "passive+no_connect"))
    )
  )
)
